# zx81_kbd_v0_2.net
KiCad netlist of a schematic drawn in EAGLE
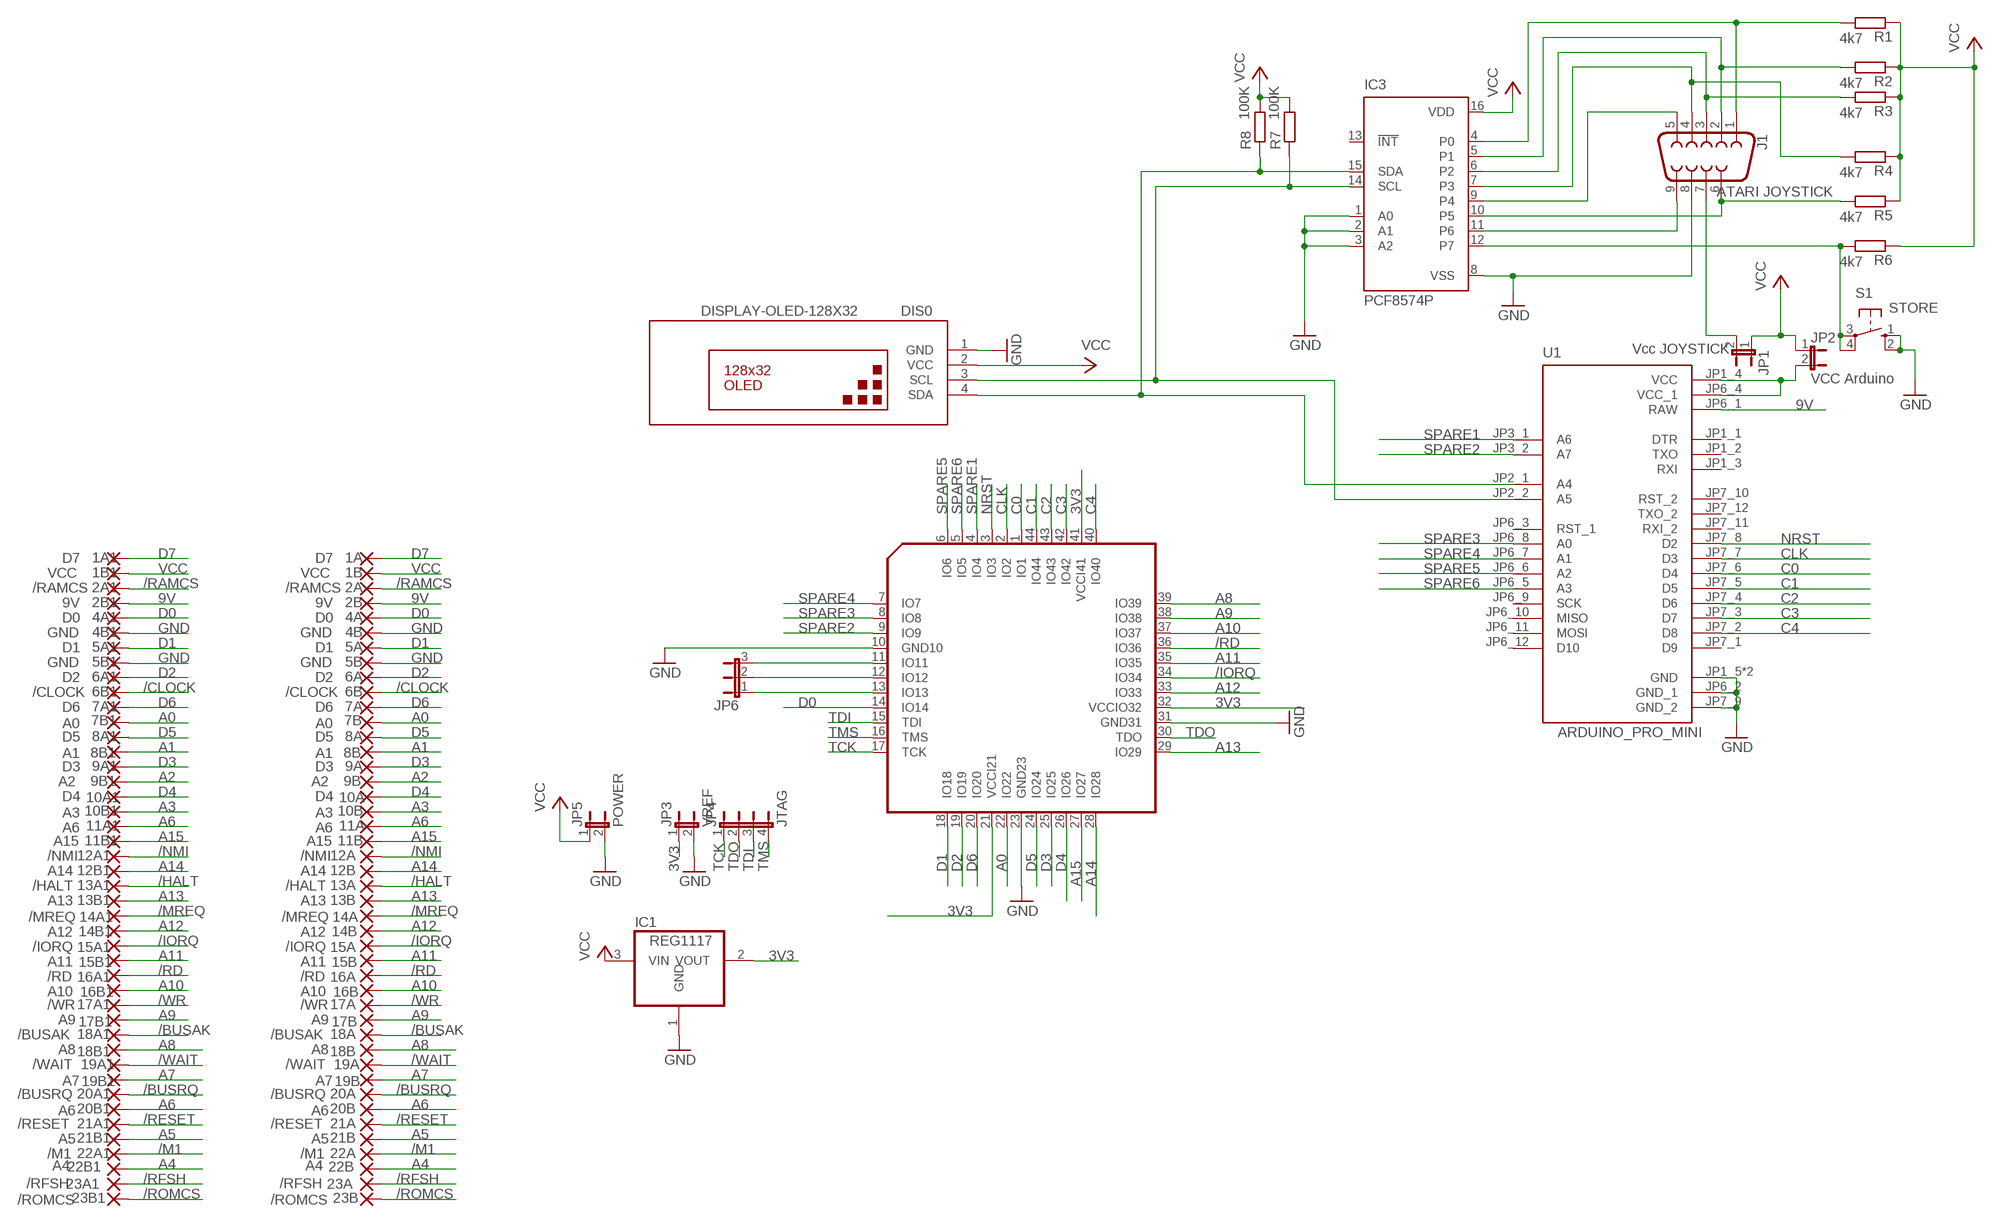
[diagram p0: schematic, sheet 1]

(export (version "E")
  (design (tool "Eeschema 10.0.6"))
  (components
    (comp (ref "1A")
      (value "D7")
      (footprint "eagle-import:EDGEPIN")
      (libsource (lib "eagle-import") (part "SMD2EDGEPIN"))
    )
    (comp (ref "1A1")
      (value "D7")
      (footprint "eagle-import:EDGEPIN")
      (libsource (lib "eagle-import") (part "SMD2EDGEPIN"))
    )
    (comp (ref "1B")
      (value "VCC")
      (footprint "eagle-import:EDGEPIN")
      (libsource (lib "eagle-import") (part "SMD2EDGEPIN"))
    )
    (comp (ref "1B1")
      (value "VCC")
      (footprint "eagle-import:EDGEPIN")
      (libsource (lib "eagle-import") (part "SMD2EDGEPIN"))
    )
    (comp (ref "2A")
      (value "/RAMCS")
      (footprint "eagle-import:EDGEPIN")
      (libsource (lib "eagle-import") (part "SMD2EDGEPIN"))
    )
    (comp (ref "2A1")
      (value "/RAMCS")
      (footprint "eagle-import:EDGEPIN")
      (libsource (lib "eagle-import") (part "SMD2EDGEPIN"))
    )
    (comp (ref "2B")
      (value "9V")
      (footprint "eagle-import:EDGEPIN")
      (libsource (lib "eagle-import") (part "SMD2EDGEPIN"))
    )
    (comp (ref "2B1")
      (value "9V")
      (footprint "eagle-import:EDGEPIN")
      (libsource (lib "eagle-import") (part "SMD2EDGEPIN"))
    )
    (comp (ref "4A")
      (value "D0")
      (footprint "eagle-import:EDGEPIN")
      (libsource (lib "eagle-import") (part "SMD2EDGEPIN"))
    )
    (comp (ref "4A1")
      (value "D0")
      (footprint "eagle-import:EDGEPIN")
      (libsource (lib "eagle-import") (part "SMD2EDGEPIN"))
    )
    (comp (ref "4B")
      (value "GND")
      (footprint "eagle-import:EDGEPIN")
      (libsource (lib "eagle-import") (part "SMD2EDGEPIN"))
    )
    (comp (ref "4B1")
      (value "GND")
      (footprint "eagle-import:EDGEPIN")
      (libsource (lib "eagle-import") (part "SMD2EDGEPIN"))
    )
    (comp (ref "5A")
      (value "D1")
      (footprint "eagle-import:EDGEPIN")
      (libsource (lib "eagle-import") (part "SMD2EDGEPIN"))
    )
    (comp (ref "5A1")
      (value "D1")
      (footprint "eagle-import:EDGEPIN")
      (libsource (lib "eagle-import") (part "SMD2EDGEPIN"))
    )
    (comp (ref "5B")
      (value "GND")
      (footprint "eagle-import:EDGEPIN")
      (libsource (lib "eagle-import") (part "SMD2EDGEPIN"))
    )
    (comp (ref "5B1")
      (value "GND")
      (footprint "eagle-import:EDGEPIN")
      (libsource (lib "eagle-import") (part "SMD2EDGEPIN"))
    )
    (comp (ref "6A")
      (value "D2")
      (footprint "eagle-import:EDGEPIN")
      (libsource (lib "eagle-import") (part "SMD2EDGEPIN"))
    )
    (comp (ref "6A1")
      (value "D2")
      (footprint "eagle-import:EDGEPIN")
      (libsource (lib "eagle-import") (part "SMD2EDGEPIN"))
    )
    (comp (ref "6B")
      (value "/CLOCK")
      (footprint "eagle-import:EDGEPIN")
      (libsource (lib "eagle-import") (part "SMD2EDGEPIN"))
    )
    (comp (ref "6B1")
      (value "/CLOCK")
      (footprint "eagle-import:EDGEPIN")
      (libsource (lib "eagle-import") (part "SMD2EDGEPIN"))
    )
    (comp (ref "7A")
      (value "D6")
      (footprint "eagle-import:EDGEPIN")
      (libsource (lib "eagle-import") (part "SMD2EDGEPIN"))
    )
    (comp (ref "7A1")
      (value "D6")
      (footprint "eagle-import:EDGEPIN")
      (libsource (lib "eagle-import") (part "SMD2EDGEPIN"))
    )
    (comp (ref "7B")
      (value "A0")
      (footprint "eagle-import:EDGEPIN")
      (libsource (lib "eagle-import") (part "SMD2EDGEPIN"))
    )
    (comp (ref "7B1")
      (value "A0")
      (footprint "eagle-import:EDGEPIN")
      (libsource (lib "eagle-import") (part "SMD2EDGEPIN"))
    )
    (comp (ref "8A")
      (value "D5")
      (footprint "eagle-import:EDGEPIN")
      (libsource (lib "eagle-import") (part "SMD2EDGEPIN"))
    )
    (comp (ref "8A1")
      (value "D5")
      (footprint "eagle-import:EDGEPIN")
      (libsource (lib "eagle-import") (part "SMD2EDGEPIN"))
    )
    (comp (ref "8B")
      (value "A1")
      (footprint "eagle-import:EDGEPIN")
      (libsource (lib "eagle-import") (part "SMD2EDGEPIN"))
    )
    (comp (ref "8B1")
      (value "A1")
      (footprint "eagle-import:EDGEPIN")
      (libsource (lib "eagle-import") (part "SMD2EDGEPIN"))
    )
    (comp (ref "9A")
      (value "D3")
      (footprint "eagle-import:EDGEPIN")
      (libsource (lib "eagle-import") (part "SMD2EDGEPIN"))
    )
    (comp (ref "9A1")
      (value "D3")
      (footprint "eagle-import:EDGEPIN")
      (libsource (lib "eagle-import") (part "SMD2EDGEPIN"))
    )
    (comp (ref "9B")
      (value "A2")
      (footprint "eagle-import:EDGEPIN")
      (libsource (lib "eagle-import") (part "SMD2EDGEPIN"))
    )
    (comp (ref "9B1")
      (value "A2")
      (footprint "eagle-import:EDGEPIN")
      (libsource (lib "eagle-import") (part "SMD2EDGEPIN"))
    )
    (comp (ref "10A")
      (value "D4")
      (footprint "eagle-import:EDGEPIN")
      (libsource (lib "eagle-import") (part "SMD2EDGEPIN"))
    )
    (comp (ref "10A1")
      (value "D4")
      (footprint "eagle-import:EDGEPIN")
      (libsource (lib "eagle-import") (part "SMD2EDGEPIN"))
    )
    (comp (ref "10B")
      (value "A3")
      (footprint "eagle-import:EDGEPIN")
      (libsource (lib "eagle-import") (part "SMD2EDGEPIN"))
    )
    (comp (ref "10B1")
      (value "A3")
      (footprint "eagle-import:EDGEPIN")
      (libsource (lib "eagle-import") (part "SMD2EDGEPIN"))
    )
    (comp (ref "11A")
      (value "A6")
      (footprint "eagle-import:EDGEPIN")
      (libsource (lib "eagle-import") (part "SMD2EDGEPIN"))
    )
    (comp (ref "11A1")
      (value "A6")
      (footprint "eagle-import:EDGEPIN")
      (libsource (lib "eagle-import") (part "SMD2EDGEPIN"))
    )
    (comp (ref "11B")
      (value "A15")
      (footprint "eagle-import:EDGEPIN")
      (libsource (lib "eagle-import") (part "SMD2EDGEPIN"))
    )
    (comp (ref "11B1")
      (value "A15")
      (footprint "eagle-import:EDGEPIN")
      (libsource (lib "eagle-import") (part "SMD2EDGEPIN"))
    )
    (comp (ref "12A")
      (value "/NMI")
      (footprint "eagle-import:EDGEPIN")
      (libsource (lib "eagle-import") (part "SMD2EDGEPIN"))
    )
    (comp (ref "12A1")
      (value "/NMI")
      (footprint "eagle-import:EDGEPIN")
      (libsource (lib "eagle-import") (part "SMD2EDGEPIN"))
    )
    (comp (ref "12B")
      (value "A14")
      (footprint "eagle-import:EDGEPIN")
      (libsource (lib "eagle-import") (part "SMD2EDGEPIN"))
    )
    (comp (ref "12B1")
      (value "A14")
      (footprint "eagle-import:EDGEPIN")
      (libsource (lib "eagle-import") (part "SMD2EDGEPIN"))
    )
    (comp (ref "13A")
      (value "/HALT")
      (footprint "eagle-import:EDGEPIN")
      (libsource (lib "eagle-import") (part "SMD2EDGEPIN"))
    )
    (comp (ref "13A1")
      (value "/HALT")
      (footprint "eagle-import:EDGEPIN")
      (libsource (lib "eagle-import") (part "SMD2EDGEPIN"))
    )
    (comp (ref "13B")
      (value "A13")
      (footprint "eagle-import:EDGEPIN")
      (libsource (lib "eagle-import") (part "SMD2EDGEPIN"))
    )
    (comp (ref "13B1")
      (value "A13")
      (footprint "eagle-import:EDGEPIN")
      (libsource (lib "eagle-import") (part "SMD2EDGEPIN"))
    )
    (comp (ref "14A")
      (value "/MREQ")
      (footprint "eagle-import:EDGEPIN")
      (libsource (lib "eagle-import") (part "SMD2EDGEPIN"))
    )
    (comp (ref "14A1")
      (value "/MREQ")
      (footprint "eagle-import:EDGEPIN")
      (libsource (lib "eagle-import") (part "SMD2EDGEPIN"))
    )
    (comp (ref "14B")
      (value "A12")
      (footprint "eagle-import:EDGEPIN")
      (libsource (lib "eagle-import") (part "SMD2EDGEPIN"))
    )
    (comp (ref "14B1")
      (value "A12")
      (footprint "eagle-import:EDGEPIN")
      (libsource (lib "eagle-import") (part "SMD2EDGEPIN"))
    )
    (comp (ref "15A")
      (value "/IORQ")
      (footprint "eagle-import:EDGEPIN")
      (libsource (lib "eagle-import") (part "SMD2EDGEPIN"))
    )
    (comp (ref "15A1")
      (value "/IORQ")
      (footprint "eagle-import:EDGEPIN")
      (libsource (lib "eagle-import") (part "SMD2EDGEPIN"))
    )
    (comp (ref "15B")
      (value "A11")
      (footprint "eagle-import:EDGEPIN")
      (libsource (lib "eagle-import") (part "SMD2EDGEPIN"))
    )
    (comp (ref "15B1")
      (value "A11")
      (footprint "eagle-import:EDGEPIN")
      (libsource (lib "eagle-import") (part "SMD2EDGEPIN"))
    )
    (comp (ref "16A")
      (value "/RD")
      (footprint "eagle-import:EDGEPIN")
      (libsource (lib "eagle-import") (part "SMD2EDGEPIN"))
    )
    (comp (ref "16A1")
      (value "/RD")
      (footprint "eagle-import:EDGEPIN")
      (libsource (lib "eagle-import") (part "SMD2EDGEPIN"))
    )
    (comp (ref "16B")
      (value "A10")
      (footprint "eagle-import:EDGEPIN")
      (libsource (lib "eagle-import") (part "SMD2EDGEPIN"))
    )
    (comp (ref "16B1")
      (value "A10")
      (footprint "eagle-import:EDGEPIN")
      (libsource (lib "eagle-import") (part "SMD2EDGEPIN"))
    )
    (comp (ref "17A")
      (value "/WR")
      (footprint "eagle-import:EDGEPIN")
      (libsource (lib "eagle-import") (part "SMD2EDGEPIN"))
    )
    (comp (ref "17A1")
      (value "/WR")
      (footprint "eagle-import:EDGEPIN")
      (libsource (lib "eagle-import") (part "SMD2EDGEPIN"))
    )
    (comp (ref "17B")
      (value "A9")
      (footprint "eagle-import:EDGEPIN")
      (libsource (lib "eagle-import") (part "SMD2EDGEPIN"))
    )
    (comp (ref "17B1")
      (value "A9")
      (footprint "eagle-import:EDGEPIN")
      (libsource (lib "eagle-import") (part "SMD2EDGEPIN"))
    )
    (comp (ref "18A")
      (value "/BUSAK")
      (footprint "eagle-import:EDGEPIN")
      (libsource (lib "eagle-import") (part "SMD2EDGEPIN"))
    )
    (comp (ref "18A1")
      (value "/BUSAK")
      (footprint "eagle-import:EDGEPIN")
      (libsource (lib "eagle-import") (part "SMD2EDGEPIN"))
    )
    (comp (ref "18B")
      (value "A8")
      (footprint "eagle-import:EDGEPIN")
      (libsource (lib "eagle-import") (part "SMD2EDGEPIN"))
    )
    (comp (ref "18B1")
      (value "A8")
      (footprint "eagle-import:EDGEPIN")
      (libsource (lib "eagle-import") (part "SMD2EDGEPIN"))
    )
    (comp (ref "19A")
      (value "/WAIT")
      (footprint "eagle-import:EDGEPIN")
      (libsource (lib "eagle-import") (part "SMD2EDGEPIN"))
    )
    (comp (ref "19A1")
      (value "/WAIT")
      (footprint "eagle-import:EDGEPIN")
      (libsource (lib "eagle-import") (part "SMD2EDGEPIN"))
    )
    (comp (ref "19B")
      (value "A7")
      (footprint "eagle-import:EDGEPIN")
      (libsource (lib "eagle-import") (part "SMD2EDGEPIN"))
    )
    (comp (ref "19B1")
      (value "A7")
      (footprint "eagle-import:EDGEPIN")
      (libsource (lib "eagle-import") (part "SMD2EDGEPIN"))
    )
    (comp (ref "20A")
      (value "/BUSRQ")
      (footprint "eagle-import:EDGEPIN")
      (libsource (lib "eagle-import") (part "SMD2EDGEPIN"))
    )
    (comp (ref "20A1")
      (value "/BUSRQ")
      (footprint "eagle-import:EDGEPIN")
      (libsource (lib "eagle-import") (part "SMD2EDGEPIN"))
    )
    (comp (ref "20B")
      (value "A6")
      (footprint "eagle-import:EDGEPIN")
      (libsource (lib "eagle-import") (part "SMD2EDGEPIN"))
    )
    (comp (ref "20B1")
      (value "A6")
      (footprint "eagle-import:EDGEPIN")
      (libsource (lib "eagle-import") (part "SMD2EDGEPIN"))
    )
    (comp (ref "21A")
      (value "/RESET")
      (footprint "eagle-import:EDGEPIN")
      (libsource (lib "eagle-import") (part "SMD2EDGEPIN"))
    )
    (comp (ref "21A1")
      (value "/RESET")
      (footprint "eagle-import:EDGEPIN")
      (libsource (lib "eagle-import") (part "SMD2EDGEPIN"))
    )
    (comp (ref "21B")
      (value "A5")
      (footprint "eagle-import:EDGEPIN")
      (libsource (lib "eagle-import") (part "SMD2EDGEPIN"))
    )
    (comp (ref "21B1")
      (value "A5")
      (footprint "eagle-import:EDGEPIN")
      (libsource (lib "eagle-import") (part "SMD2EDGEPIN"))
    )
    (comp (ref "22A")
      (value "/M1")
      (footprint "eagle-import:EDGEPIN")
      (libsource (lib "eagle-import") (part "SMD2EDGEPIN"))
    )
    (comp (ref "22A1")
      (value "/M1")
      (footprint "eagle-import:EDGEPIN")
      (libsource (lib "eagle-import") (part "SMD2EDGEPIN"))
    )
    (comp (ref "22B")
      (value "A4")
      (footprint "eagle-import:EDGEPIN")
      (libsource (lib "eagle-import") (part "SMD2EDGEPIN"))
    )
    (comp (ref "22B1")
      (value "A4")
      (footprint "eagle-import:EDGEPIN")
      (libsource (lib "eagle-import") (part "SMD2EDGEPIN"))
    )
    (comp (ref "23A")
      (value "/RFSH")
      (footprint "eagle-import:EDGEPIN")
      (libsource (lib "eagle-import") (part "SMD2EDGEPIN"))
    )
    (comp (ref "23A1")
      (value "/RFSH")
      (footprint "eagle-import:EDGEPIN")
      (libsource (lib "eagle-import") (part "SMD2EDGEPIN"))
    )
    (comp (ref "23B")
      (value "/ROMCS")
      (footprint "eagle-import:EDGEPIN")
      (libsource (lib "eagle-import") (part "SMD2EDGEPIN"))
    )
    (comp (ref "23B1")
      (value "/ROMCS")
      (footprint "eagle-import:EDGEPIN")
      (libsource (lib "eagle-import") (part "SMD2EDGEPIN"))
    )
    (comp (ref "DIS0")
      (value "DISPLAY-OLED-128X32")
      (footprint "eagle-import:DISPLAY-OLED-128X32")
      (libsource (lib "eagle-import") (part "DISPLAY-OLED-128X32"))
    )
    (comp (ref "IC1")
      (value "REG1117")
      (footprint "eagle-import:SOT223")
      (libsource (lib "eagle-import") (part "REG1117"))
    )
    (comp (ref "IC3")
      (value "PCF8574P")
      (footprint "eagle-import:DIL16")
      (fields (field (name "MPN") "PCF8574PN"))
      (libsource (lib "eagle-import") (part "PCF8574P"))
    )
    (comp (ref "J1")
      (value "ATARI JOYSTICK")
      (footprint "eagle-import:DB9_MALE")
      (libsource (lib "eagle-import") (part "DB9MALE"))
    )
    (comp (ref "JP1")
      (value "Vcc JOYSTICK")
      (footprint "eagle-import:JP1")
      (libsource (lib "eagle-import") (part "JP1E"))
    )
    (comp (ref "JP2")
      (value "VCC Arduino")
      (footprint "eagle-import:JP1")
      (libsource (lib "eagle-import") (part "JP1E"))
    )
    (comp (ref "JP3")
      (value "VREF")
      (footprint "eagle-import:JP1")
      (libsource (lib "eagle-import") (part "jumper_35741532_JP1E"))
    )
    (comp (ref "JP4")
      (value "JTAG")
      (footprint "eagle-import:JP4")
      (libsource (lib "eagle-import") (part "JP4E"))
    )
    (comp (ref "JP5")
      (value "POWER")
      (footprint "eagle-import:JP1")
      (libsource (lib "eagle-import") (part "jumper_35741532_JP1E"))
    )
    (comp (ref "JP6")
      (value "JP2E")
      (footprint "eagle-import:JP2")
      (libsource (lib "eagle-import") (part "JP2E"))
    )
    (comp (ref "R1")
      (value "4k7")
      (footprint "eagle-import:0204_7")
      (libsource (lib "eagle-import") (part "R-EU_0204/7"))
    )
    (comp (ref "R2")
      (value "4k7")
      (footprint "eagle-import:0204_7")
      (libsource (lib "eagle-import") (part "R-EU_0204/7"))
    )
    (comp (ref "R3")
      (value "4k7")
      (footprint "eagle-import:0204_7")
      (libsource (lib "eagle-import") (part "R-EU_0204/7"))
    )
    (comp (ref "R4")
      (value "4k7")
      (footprint "eagle-import:0204_7")
      (libsource (lib "eagle-import") (part "R-EU_0204/7"))
    )
    (comp (ref "R5")
      (value "4k7")
      (footprint "eagle-import:0204_7")
      (libsource (lib "eagle-import") (part "R-EU_0204/7"))
    )
    (comp (ref "R6")
      (value "4k7")
      (footprint "eagle-import:0204_7")
      (libsource (lib "eagle-import") (part "R-EU_0204/7"))
    )
    (comp (ref "R7")
      (value "100K")
      (footprint "eagle-import:0204_7")
      (libsource (lib "eagle-import") (part "R-EU_0204/7"))
    )
    (comp (ref "R8")
      (value "100K")
      (footprint "eagle-import:0204_7")
      (libsource (lib "eagle-import") (part "R-EU_0204/7"))
    )
    (comp (ref "S1")
      (value "STORE")
      (footprint "eagle-import:B3F-10XX_11MM")
      (libsource (lib "eagle-import") (part "10-XX11MM"))
    )
    (comp (ref "U1")
      (value "ARDUINO_PRO_MINI")
      (footprint "eagle-import:MODULE_ARDUINO_PRO_MINI")
      (fields (field (name "MF") "Arduino") (field (name "MP") "Arduino Pro Mini"))
      (libsource (lib "eagle-import") (part "ARDUINO_PRO_MINI"))
    )
    (comp (ref "XC95CPLD")
      (value "XC9572PLC")
      (footprint "eagle-import:3M44")
      (libsource (lib "eagle-import") (part "XC9572PLC"))
    )
  )
  (nets
    (net (code "1") (name "/3V3") (class "Default")
      (node (ref "IC1") (pin "2") (pinfunction "VOUT_2") (pintype "output"))
      (node (ref "JP3") (pin "1") (pinfunction "1_1") (pintype "passive"))
      (node (ref "XC95CPLD") (pin "21") (pinfunction "VCCI21_21") (pintype "power_in"))
      (node (ref "XC95CPLD") (pin "32") (pinfunction "VCCIO32_32") (pintype "power_in"))
      (node (ref "XC95CPLD") (pin "41") (pinfunction "VCCI41_41") (pintype "power_in"))
    )
    (net (code "2") (name "/9V") (class "Default")
      (node (ref "2B") (pin "1") (pinfunction "P_1") (pintype "passive"))
      (node (ref "2B1") (pin "1") (pinfunction "P_1") (pintype "passive"))
      (node (ref "U1") (pin "JP6_1") (pinfunction "RAW_JP6_1") (pintype "power_in"))
    )
    (net (code "3") (name "/A0") (class "Default")
      (node (ref "7B") (pin "1") (pinfunction "P_1") (pintype "passive"))
      (node (ref "7B1") (pin "1") (pinfunction "P_1") (pintype "passive"))
      (node (ref "XC95CPLD") (pin "22") (pinfunction "IO22_22") (pintype "bidirectional"))
    )
    (net (code "4") (name "/A1") (class "Default")
      (node (ref "8B") (pin "1") (pinfunction "P_1") (pintype "passive"))
      (node (ref "8B1") (pin "1") (pinfunction "P_1") (pintype "passive"))
    )
    (net (code "5") (name "/A2") (class "Default")
      (node (ref "9B") (pin "1") (pinfunction "P_1") (pintype "passive"))
      (node (ref "9B1") (pin "1") (pinfunction "P_1") (pintype "passive"))
    )
    (net (code "6") (name "/A3") (class "Default")
      (node (ref "10B") (pin "1") (pinfunction "P_1") (pintype "passive"))
      (node (ref "10B1") (pin "1") (pinfunction "P_1") (pintype "passive"))
    )
    (net (code "7") (name "/A4") (class "Default")
      (node (ref "22B") (pin "1") (pinfunction "P_1") (pintype "passive"))
      (node (ref "22B1") (pin "1") (pinfunction "P_1") (pintype "passive"))
    )
    (net (code "8") (name "/A5") (class "Default")
      (node (ref "21B") (pin "1") (pinfunction "P_1") (pintype "passive"))
      (node (ref "21B1") (pin "1") (pinfunction "P_1") (pintype "passive"))
    )
    (net (code "9") (name "/A6") (class "Default")
      (node (ref "11A") (pin "1") (pinfunction "P_1") (pintype "passive"))
      (node (ref "11A1") (pin "1") (pinfunction "P_1") (pintype "passive"))
      (node (ref "20B") (pin "1") (pinfunction "P_1") (pintype "passive"))
      (node (ref "20B1") (pin "1") (pinfunction "P_1") (pintype "passive"))
    )
    (net (code "10") (name "/A7") (class "Default")
      (node (ref "19B") (pin "1") (pinfunction "P_1") (pintype "passive"))
      (node (ref "19B1") (pin "1") (pinfunction "P_1") (pintype "passive"))
    )
    (net (code "11") (name "/A8") (class "Default")
      (node (ref "18B") (pin "1") (pinfunction "P_1") (pintype "passive"))
      (node (ref "18B1") (pin "1") (pinfunction "P_1") (pintype "passive"))
      (node (ref "XC95CPLD") (pin "39") (pinfunction "IO39_39") (pintype "bidirectional"))
    )
    (net (code "12") (name "/A9") (class "Default")
      (node (ref "17B") (pin "1") (pinfunction "P_1") (pintype "passive"))
      (node (ref "17B1") (pin "1") (pinfunction "P_1") (pintype "passive"))
      (node (ref "XC95CPLD") (pin "38") (pinfunction "IO38_38") (pintype "bidirectional"))
    )
    (net (code "13") (name "/A10") (class "Default")
      (node (ref "16B") (pin "1") (pinfunction "P_1") (pintype "passive"))
      (node (ref "16B1") (pin "1") (pinfunction "P_1") (pintype "passive"))
      (node (ref "XC95CPLD") (pin "37") (pinfunction "IO37_37") (pintype "bidirectional"))
    )
    (net (code "14") (name "/A11") (class "Default")
      (node (ref "15B") (pin "1") (pinfunction "P_1") (pintype "passive"))
      (node (ref "15B1") (pin "1") (pinfunction "P_1") (pintype "passive"))
      (node (ref "XC95CPLD") (pin "35") (pinfunction "IO35_35") (pintype "bidirectional"))
    )
    (net (code "15") (name "/A12") (class "Default")
      (node (ref "14B") (pin "1") (pinfunction "P_1") (pintype "passive"))
      (node (ref "14B1") (pin "1") (pinfunction "P_1") (pintype "passive"))
      (node (ref "XC95CPLD") (pin "33") (pinfunction "IO33_33") (pintype "bidirectional"))
    )
    (net (code "16") (name "/A13") (class "Default")
      (node (ref "13B") (pin "1") (pinfunction "P_1") (pintype "passive"))
      (node (ref "13B1") (pin "1") (pinfunction "P_1") (pintype "passive"))
      (node (ref "XC95CPLD") (pin "29") (pinfunction "IO29_29") (pintype "bidirectional"))
    )
    (net (code "17") (name "/A14") (class "Default")
      (node (ref "12B") (pin "1") (pinfunction "P_1") (pintype "passive"))
      (node (ref "12B1") (pin "1") (pinfunction "P_1") (pintype "passive"))
      (node (ref "XC95CPLD") (pin "28") (pinfunction "IO28_28") (pintype "bidirectional"))
    )
    (net (code "18") (name "/A15") (class "Default")
      (node (ref "11B") (pin "1") (pinfunction "P_1") (pintype "passive"))
      (node (ref "11B1") (pin "1") (pinfunction "P_1") (pintype "passive"))
      (node (ref "XC95CPLD") (pin "27") (pinfunction "IO27_27") (pintype "bidirectional"))
    )
    (net (code "19") (name "/C0") (class "Default")
      (node (ref "U1") (pin "JP7_6") (pinfunction "D4_JP7_6") (pintype "bidirectional"))
      (node (ref "XC95CPLD") (pin "1") (pinfunction "IO1_1") (pintype "bidirectional"))
    )
    (net (code "20") (name "/C1") (class "Default")
      (node (ref "U1") (pin "JP7_5") (pinfunction "D5_JP7_5") (pintype "bidirectional"))
      (node (ref "XC95CPLD") (pin "44") (pinfunction "IO44_44") (pintype "bidirectional"))
    )
    (net (code "21") (name "/C2") (class "Default")
      (node (ref "U1") (pin "JP7_4") (pinfunction "D6_JP7_4") (pintype "bidirectional"))
      (node (ref "XC95CPLD") (pin "43") (pinfunction "IO43_43") (pintype "bidirectional"))
    )
    (net (code "22") (name "/C3") (class "Default")
      (node (ref "U1") (pin "JP7_3") (pinfunction "D7_JP7_3") (pintype "bidirectional"))
      (node (ref "XC95CPLD") (pin "42") (pinfunction "IO42_42") (pintype "bidirectional"))
    )
    (net (code "23") (name "/C4") (class "Default")
      (node (ref "U1") (pin "JP7_2") (pinfunction "D8_JP7_2") (pintype "bidirectional"))
      (node (ref "XC95CPLD") (pin "40") (pinfunction "IO40_40") (pintype "bidirectional"))
    )
    (net (code "24") (name "/CLK") (class "Default")
      (node (ref "U1") (pin "JP7_7") (pinfunction "D3_JP7_7") (pintype "bidirectional"))
      (node (ref "XC95CPLD") (pin "2") (pinfunction "IO2_2") (pintype "bidirectional"))
    )
    (net (code "25") (name "/D0") (class "Default")
      (node (ref "4A") (pin "1") (pinfunction "P_1") (pintype "passive"))
      (node (ref "4A1") (pin "1") (pinfunction "P_1") (pintype "passive"))
      (node (ref "XC95CPLD") (pin "14") (pinfunction "IO14_14") (pintype "bidirectional"))
    )
    (net (code "26") (name "/D1") (class "Default")
      (node (ref "5A") (pin "1") (pinfunction "P_1") (pintype "passive"))
      (node (ref "5A1") (pin "1") (pinfunction "P_1") (pintype "passive"))
      (node (ref "XC95CPLD") (pin "18") (pinfunction "IO18_18") (pintype "bidirectional"))
    )
    (net (code "27") (name "/D2") (class "Default")
      (node (ref "6A") (pin "1") (pinfunction "P_1") (pintype "passive"))
      (node (ref "6A1") (pin "1") (pinfunction "P_1") (pintype "passive"))
      (node (ref "XC95CPLD") (pin "19") (pinfunction "IO19_19") (pintype "bidirectional"))
    )
    (net (code "28") (name "/D3") (class "Default")
      (node (ref "9A") (pin "1") (pinfunction "P_1") (pintype "passive"))
      (node (ref "9A1") (pin "1") (pinfunction "P_1") (pintype "passive"))
      (node (ref "XC95CPLD") (pin "25") (pinfunction "IO25_25") (pintype "bidirectional"))
    )
    (net (code "29") (name "/D4") (class "Default")
      (node (ref "10A") (pin "1") (pinfunction "P_1") (pintype "passive"))
      (node (ref "10A1") (pin "1") (pinfunction "P_1") (pintype "passive"))
      (node (ref "XC95CPLD") (pin "26") (pinfunction "IO26_26") (pintype "bidirectional"))
    )
    (net (code "30") (name "/D5") (class "Default")
      (node (ref "8A") (pin "1") (pinfunction "P_1") (pintype "passive"))
      (node (ref "8A1") (pin "1") (pinfunction "P_1") (pintype "passive"))
      (node (ref "XC95CPLD") (pin "24") (pinfunction "IO24_24") (pintype "bidirectional"))
    )
    (net (code "31") (name "/D6") (class "Default")
      (node (ref "7A") (pin "1") (pinfunction "P_1") (pintype "passive"))
      (node (ref "7A1") (pin "1") (pinfunction "P_1") (pintype "passive"))
      (node (ref "XC95CPLD") (pin "20") (pinfunction "IO20_20") (pintype "bidirectional"))
    )
    (net (code "32") (name "/D7") (class "Default")
      (node (ref "1A") (pin "1") (pinfunction "P_1") (pintype "passive"))
      (node (ref "1A1") (pin "1") (pinfunction "P_1") (pintype "passive"))
    )
    (net (code "33") (name "/NRST") (class "Default")
      (node (ref "U1") (pin "JP7_8") (pinfunction "D2_JP7_8") (pintype "bidirectional"))
      (node (ref "XC95CPLD") (pin "3") (pinfunction "IO3_3") (pintype "bidirectional"))
    )
    (net (code "34") (name "/SPARE1") (class "Default")
      (node (ref "U1") (pin "JP3_1") (pinfunction "A6_JP3_1") (pintype "input"))
      (node (ref "XC95CPLD") (pin "4") (pinfunction "IO4_4") (pintype "bidirectional"))
    )
    (net (code "35") (name "/SPARE2") (class "Default")
      (node (ref "U1") (pin "JP3_2") (pinfunction "A7_JP3_2") (pintype "input"))
      (node (ref "XC95CPLD") (pin "9") (pinfunction "IO9_9") (pintype "bidirectional"))
    )
    (net (code "36") (name "/SPARE3") (class "Default")
      (node (ref "U1") (pin "JP6_8") (pinfunction "A0_JP6_8") (pintype "bidirectional"))
      (node (ref "XC95CPLD") (pin "8") (pinfunction "IO8_8") (pintype "bidirectional"))
    )
    (net (code "37") (name "/SPARE4") (class "Default")
      (node (ref "U1") (pin "JP6_7") (pinfunction "A1_JP6_7") (pintype "bidirectional"))
      (node (ref "XC95CPLD") (pin "7") (pinfunction "IO7_7") (pintype "bidirectional"))
    )
    (net (code "38") (name "/SPARE5") (class "Default")
      (node (ref "U1") (pin "JP6_6") (pinfunction "A2_JP6_6") (pintype "bidirectional"))
      (node (ref "XC95CPLD") (pin "6") (pinfunction "IO6_6") (pintype "bidirectional"))
    )
    (net (code "39") (name "/SPARE6") (class "Default")
      (node (ref "U1") (pin "JP6_5") (pinfunction "A3_JP6_5") (pintype "bidirectional"))
      (node (ref "XC95CPLD") (pin "5") (pinfunction "IO5_5") (pintype "bidirectional"))
    )
    (net (code "40") (name "/TCK") (class "Default")
      (node (ref "JP4") (pin "1") (pinfunction "1_1") (pintype "passive"))
      (node (ref "XC95CPLD") (pin "17") (pinfunction "TCK_17") (pintype "passive"))
    )
    (net (code "41") (name "/TDI") (class "Default")
      (node (ref "JP4") (pin "3") (pinfunction "3_3") (pintype "passive"))
      (node (ref "XC95CPLD") (pin "15") (pinfunction "TDI_15") (pintype "passive"))
    )
    (net (code "42") (name "/TDO") (class "Default")
      (node (ref "JP4") (pin "2") (pinfunction "2_2") (pintype "passive"))
      (node (ref "XC95CPLD") (pin "30") (pinfunction "TDO_30") (pintype "passive"))
    )
    (net (code "43") (name "/TMS") (class "Default")
      (node (ref "JP4") (pin "4") (pinfunction "4_4") (pintype "passive"))
      (node (ref "XC95CPLD") (pin "16") (pinfunction "TMS_16") (pintype "passive"))
    )
    (net (code "44") (name "/{slash}BUSAK") (class "Default")
      (node (ref "18A") (pin "1") (pinfunction "P_1") (pintype "passive"))
      (node (ref "18A1") (pin "1") (pinfunction "P_1") (pintype "passive"))
    )
    (net (code "45") (name "/{slash}BUSRQ") (class "Default")
      (node (ref "20A") (pin "1") (pinfunction "P_1") (pintype "passive"))
      (node (ref "20A1") (pin "1") (pinfunction "P_1") (pintype "passive"))
    )
    (net (code "46") (name "/{slash}CLOCK") (class "Default")
      (node (ref "6B") (pin "1") (pinfunction "P_1") (pintype "passive"))
      (node (ref "6B1") (pin "1") (pinfunction "P_1") (pintype "passive"))
    )
    (net (code "47") (name "/{slash}HALT") (class "Default")
      (node (ref "13A") (pin "1") (pinfunction "P_1") (pintype "passive"))
      (node (ref "13A1") (pin "1") (pinfunction "P_1") (pintype "passive"))
    )
    (net (code "48") (name "/{slash}IORQ") (class "Default")
      (node (ref "15A") (pin "1") (pinfunction "P_1") (pintype "passive"))
      (node (ref "15A1") (pin "1") (pinfunction "P_1") (pintype "passive"))
      (node (ref "XC95CPLD") (pin "34") (pinfunction "IO34_34") (pintype "bidirectional"))
    )
    (net (code "49") (name "/{slash}M1") (class "Default")
      (node (ref "22A") (pin "1") (pinfunction "P_1") (pintype "passive"))
      (node (ref "22A1") (pin "1") (pinfunction "P_1") (pintype "passive"))
    )
    (net (code "50") (name "/{slash}MREQ") (class "Default")
      (node (ref "14A") (pin "1") (pinfunction "P_1") (pintype "passive"))
      (node (ref "14A1") (pin "1") (pinfunction "P_1") (pintype "passive"))
    )
    (net (code "51") (name "/{slash}NMI") (class "Default")
      (node (ref "12A") (pin "1") (pinfunction "P_1") (pintype "passive"))
      (node (ref "12A1") (pin "1") (pinfunction "P_1") (pintype "passive"))
    )
    (net (code "52") (name "/{slash}RAMCS") (class "Default")
      (node (ref "2A") (pin "1") (pinfunction "P_1") (pintype "passive"))
      (node (ref "2A1") (pin "1") (pinfunction "P_1") (pintype "passive"))
    )
    (net (code "53") (name "/{slash}RD") (class "Default")
      (node (ref "16A") (pin "1") (pinfunction "P_1") (pintype "passive"))
      (node (ref "16A1") (pin "1") (pinfunction "P_1") (pintype "passive"))
      (node (ref "XC95CPLD") (pin "36") (pinfunction "IO36_36") (pintype "bidirectional"))
    )
    (net (code "54") (name "/{slash}RESET") (class "Default")
      (node (ref "21A") (pin "1") (pinfunction "P_1") (pintype "passive"))
      (node (ref "21A1") (pin "1") (pinfunction "P_1") (pintype "passive"))
    )
    (net (code "55") (name "/{slash}RFSH") (class "Default")
      (node (ref "23A") (pin "1") (pinfunction "P_1") (pintype "passive"))
      (node (ref "23A1") (pin "1") (pinfunction "P_1") (pintype "passive"))
    )
    (net (code "56") (name "/{slash}ROMCS") (class "Default")
      (node (ref "23B") (pin "1") (pinfunction "P_1") (pintype "passive"))
      (node (ref "23B1") (pin "1") (pinfunction "P_1") (pintype "passive"))
    )
    (net (code "57") (name "/{slash}WAIT") (class "Default")
      (node (ref "19A") (pin "1") (pinfunction "P_1") (pintype "passive"))
      (node (ref "19A1") (pin "1") (pinfunction "P_1") (pintype "passive"))
    )
    (net (code "58") (name "/{slash}WR") (class "Default")
      (node (ref "17A") (pin "1") (pinfunction "P_1") (pintype "passive"))
      (node (ref "17A1") (pin "1") (pinfunction "P_1") (pintype "passive"))
    )
    (net (code "59") (name "GND") (class "Default")
      (node (ref "4B") (pin "1") (pinfunction "P_1") (pintype "passive"))
      (node (ref "4B1") (pin "1") (pinfunction "P_1") (pintype "passive"))
      (node (ref "5B") (pin "1") (pinfunction "P_1") (pintype "passive"))
      (node (ref "5B1") (pin "1") (pinfunction "P_1") (pintype "passive"))
      (node (ref "DIS0") (pin "1") (pinfunction "GND_1") (pintype "power_in"))
      (node (ref "IC1") (pin "1") (pinfunction "GND_1") (pintype "power_in"))
      (node (ref "IC3") (pin "1") (pinfunction "A0_1") (pintype "input"))
      (node (ref "IC3") (pin "2") (pinfunction "A1_2") (pintype "input"))
      (node (ref "IC3") (pin "3") (pinfunction "A2_3") (pintype "input"))
      (node (ref "IC3") (pin "8") (pinfunction "VSS_8") (pintype "power_in"))
      (node (ref "J1") (pin "8") (pinfunction "8_8") (pintype "passive"))
      (node (ref "JP3") (pin "2") (pinfunction "2_2") (pintype "passive"))
      (node (ref "JP5") (pin "2") (pinfunction "2_2") (pintype "passive"))
      (node (ref "S1") (pin "1") (pinfunction "S_1") (pintype "passive"))
      (node (ref "S1") (pin "2") (pinfunction "S1_2") (pintype "passive"))
      (node (ref "U1") (pin "JP1_5") (pinfunction "GND_JP1_5") (pintype "power_in"))
      (node (ref "U1") (pin "JP1_6") (pinfunction "GND_JP1_6") (pintype "power_in"))
      (node (ref "U1") (pin "JP6_2") (pinfunction "GND_1_JP6_2") (pintype "power_in"))
      (node (ref "U1") (pin "JP7_9") (pinfunction "GND_2_JP7_9") (pintype "power_in"))
      (node (ref "XC95CPLD") (pin "10") (pinfunction "GND10_10") (pintype "power_in"))
      (node (ref "XC95CPLD") (pin "23") (pinfunction "GND23_23") (pintype "power_in"))
      (node (ref "XC95CPLD") (pin "31") (pinfunction "GND31_31") (pintype "power_in"))
    )
    (net (code "60") (name "Net-(DIS0-SCL)") (class "Default")
      (node (ref "DIS0") (pin "3") (pinfunction "SCL_3") (pintype "bidirectional"))
      (node (ref "IC3") (pin "14") (pinfunction "SCL_14") (pintype "input"))
      (node (ref "R7") (pin "1") (pinfunction "1_1") (pintype "passive"))
      (node (ref "U1") (pin "JP2_2") (pinfunction "A5_JP2_2") (pintype "bidirectional"))
    )
    (net (code "61") (name "Net-(DIS0-SDA)") (class "Default")
      (node (ref "DIS0") (pin "4") (pinfunction "SDA_4") (pintype "bidirectional"))
      (node (ref "IC3") (pin "15") (pinfunction "SDA_15") (pintype "bidirectional"))
      (node (ref "R8") (pin "1") (pinfunction "1_1") (pintype "passive"))
      (node (ref "U1") (pin "JP2_1") (pinfunction "A4_JP2_1") (pintype "bidirectional"))
    )
    (net (code "62") (name "Net-(IC3-P0)") (class "Default")
      (node (ref "IC3") (pin "4") (pinfunction "P0_4") (pintype "bidirectional"))
      (node (ref "J1") (pin "1") (pinfunction "1_1") (pintype "passive"))
      (node (ref "R1") (pin "2") (pinfunction "2_2") (pintype "passive"))
    )
    (net (code "63") (name "Net-(IC3-P1)") (class "Default")
      (node (ref "IC3") (pin "5") (pinfunction "P1_5") (pintype "bidirectional"))
      (node (ref "J1") (pin "2") (pinfunction "2_2") (pintype "passive"))
      (node (ref "R2") (pin "2") (pinfunction "2_2") (pintype "passive"))
    )
    (net (code "64") (name "Net-(IC3-P2)") (class "Default")
      (node (ref "IC3") (pin "6") (pinfunction "P2_6") (pintype "bidirectional"))
      (node (ref "J1") (pin "3") (pinfunction "3_3") (pintype "passive"))
      (node (ref "R3") (pin "2") (pinfunction "2_2") (pintype "passive"))
    )
    (net (code "65") (name "Net-(IC3-P3)") (class "Default")
      (node (ref "IC3") (pin "7") (pinfunction "P3_7") (pintype "bidirectional"))
      (node (ref "J1") (pin "4") (pinfunction "4_4") (pintype "passive"))
      (node (ref "R4") (pin "2") (pinfunction "2_2") (pintype "passive"))
    )
    (net (code "66") (name "Net-(IC3-P4)") (class "Default")
      (node (ref "IC3") (pin "9") (pinfunction "P4_9") (pintype "bidirectional"))
      (node (ref "J1") (pin "5") (pinfunction "5_5") (pintype "passive"))
    )
    (net (code "67") (name "Net-(IC3-P5)") (class "Default")
      (node (ref "IC3") (pin "10") (pinfunction "P5_10") (pintype "bidirectional"))
      (node (ref "J1") (pin "6") (pinfunction "6_6") (pintype "passive"))
      (node (ref "R5") (pin "2") (pinfunction "2_2") (pintype "passive"))
    )
    (net (code "68") (name "Net-(IC3-P6)") (class "Default")
      (node (ref "IC3") (pin "11") (pinfunction "P6_11") (pintype "bidirectional"))
      (node (ref "J1") (pin "9") (pinfunction "9_9") (pintype "passive"))
    )
    (net (code "69") (name "Net-(IC3-P7)") (class "Default")
      (node (ref "IC3") (pin "12") (pinfunction "P7_12") (pintype "bidirectional"))
      (node (ref "R6") (pin "2") (pinfunction "2_2") (pintype "passive"))
      (node (ref "S1") (pin "3") (pinfunction "P_3") (pintype "passive"))
      (node (ref "S1") (pin "4") (pinfunction "P1_4") (pintype "passive"))
    )
    (net (code "70") (name "Net-(J1-Pad7)") (class "Default")
      (node (ref "J1") (pin "7") (pinfunction "7_7") (pintype "passive"))
      (node (ref "JP1") (pin "2") (pinfunction "2_2") (pintype "passive"))
    )
    (net (code "71") (name "Net-(U1-VCC)") (class "Default")
      (node (ref "JP2") (pin "2") (pinfunction "2_2") (pintype "passive"))
      (node (ref "U1") (pin "JP1_4") (pinfunction "VCC_JP1_4") (pintype "power_in"))
      (node (ref "U1") (pin "JP6_4") (pinfunction "VCC_1_JP6_4") (pintype "power_in"))
    )
    (net (code "72") (name "Net-(XC95CPLD-IO11)") (class "Default")
      (node (ref "JP6") (pin "3") (pinfunction "3_3") (pintype "passive"))
      (node (ref "XC95CPLD") (pin "11") (pinfunction "IO11_11") (pintype "bidirectional"))
    )
    (net (code "73") (name "Net-(XC95CPLD-IO12)") (class "Default")
      (node (ref "JP6") (pin "2") (pinfunction "2_2") (pintype "passive"))
      (node (ref "XC95CPLD") (pin "12") (pinfunction "IO12_12") (pintype "bidirectional"))
    )
    (net (code "74") (name "Net-(XC95CPLD-IO13)") (class "Default")
      (node (ref "JP6") (pin "1") (pinfunction "1_1") (pintype "passive"))
      (node (ref "XC95CPLD") (pin "13") (pinfunction "IO13_13") (pintype "bidirectional"))
    )
    (net (code "75") (name "VCC") (class "Default")
      (node (ref "1B") (pin "1") (pinfunction "P_1") (pintype "passive"))
      (node (ref "1B1") (pin "1") (pinfunction "P_1") (pintype "passive"))
      (node (ref "DIS0") (pin "2") (pinfunction "VCC_2") (pintype "power_in"))
      (node (ref "IC1") (pin "3") (pinfunction "VIN_3") (pintype "input"))
      (node (ref "IC3") (pin "16") (pinfunction "VDD_16") (pintype "power_in"))
      (node (ref "JP1") (pin "1") (pinfunction "1_1") (pintype "passive"))
      (node (ref "JP2") (pin "1") (pinfunction "1_1") (pintype "passive"))
      (node (ref "JP5") (pin "1") (pinfunction "1_1") (pintype "passive"))
      (node (ref "R1") (pin "1") (pinfunction "1_1") (pintype "passive"))
      (node (ref "R2") (pin "1") (pinfunction "1_1") (pintype "passive"))
      (node (ref "R3") (pin "1") (pinfunction "1_1") (pintype "passive"))
      (node (ref "R4") (pin "1") (pinfunction "1_1") (pintype "passive"))
      (node (ref "R5") (pin "1") (pinfunction "1_1") (pintype "passive"))
      (node (ref "R6") (pin "1") (pinfunction "1_1") (pintype "passive"))
      (node (ref "R7") (pin "2") (pinfunction "2_2") (pintype "passive"))
      (node (ref "R8") (pin "2") (pinfunction "2_2") (pintype "passive"))
    )
    (net (code "76") (name "unconnected-(IC3-~{INT}-Pad13)") (class "Default")
      (node (ref "IC3") (pin "13") (pinfunction "~{INT}_13") (pintype "output"))
    )
    (net (code "77") (name "unconnected-(U1-D9-PadJP7_1)") (class "Default")
      (node (ref "U1") (pin "JP7_1") (pinfunction "D9_JP7_1") (pintype "bidirectional"))
    )
    (net (code "78") (name "unconnected-(U1-D10-PadJP6_12)") (class "Default")
      (node (ref "U1") (pin "JP6_12") (pinfunction "D10_JP6_12") (pintype "bidirectional"))
    )
    (net (code "79") (name "unconnected-(U1-DTR-PadJP1_1)") (class "Default")
      (node (ref "U1") (pin "JP1_1") (pinfunction "DTR_JP1_1") (pintype "input"))
    )
    (net (code "80") (name "unconnected-(U1-MISO-PadJP6_10)") (class "Default")
      (node (ref "U1") (pin "JP6_10") (pinfunction "MISO_JP6_10") (pintype "bidirectional"))
    )
    (net (code "81") (name "unconnected-(U1-MOSI-PadJP6_11)") (class "Default")
      (node (ref "U1") (pin "JP6_11") (pinfunction "MOSI_JP6_11") (pintype "bidirectional"))
    )
    (net (code "82") (name "unconnected-(U1-RST_1-PadJP6_3)") (class "Default")
      (node (ref "U1") (pin "JP6_3") (pinfunction "RST_1_JP6_3") (pintype "input"))
    )
    (net (code "83") (name "unconnected-(U1-RST_2-PadJP7_10)") (class "Default")
      (node (ref "U1") (pin "JP7_10") (pinfunction "RST_2_JP7_10") (pintype "input"))
    )
    (net (code "84") (name "unconnected-(U1-RXI-PadJP1_3)") (class "Default")
      (node (ref "U1") (pin "JP1_3") (pinfunction "RXI_JP1_3") (pintype "bidirectional"))
    )
    (net (code "85") (name "unconnected-(U1-RXI_2-PadJP7_11)") (class "Default")
      (node (ref "U1") (pin "JP7_11") (pinfunction "RXI_2_JP7_11") (pintype "bidirectional"))
    )
    (net (code "86") (name "unconnected-(U1-SCK-PadJP6_9)") (class "Default")
      (node (ref "U1") (pin "JP6_9") (pinfunction "SCK_JP6_9") (pintype "bidirectional"))
    )
    (net (code "87") (name "unconnected-(U1-TXO-PadJP1_2)") (class "Default")
      (node (ref "U1") (pin "JP1_2") (pinfunction "TXO_JP1_2") (pintype "bidirectional"))
    )
    (net (code "88") (name "unconnected-(U1-TXO_2-PadJP7_12)") (class "Default")
      (node (ref "U1") (pin "JP7_12") (pinfunction "TXO_2_JP7_12") (pintype "bidirectional"))
    )
  )
)
